# EEPROM_Temp_LEDs.net
KiCad netlist of a schematic drawn in Altium Designer
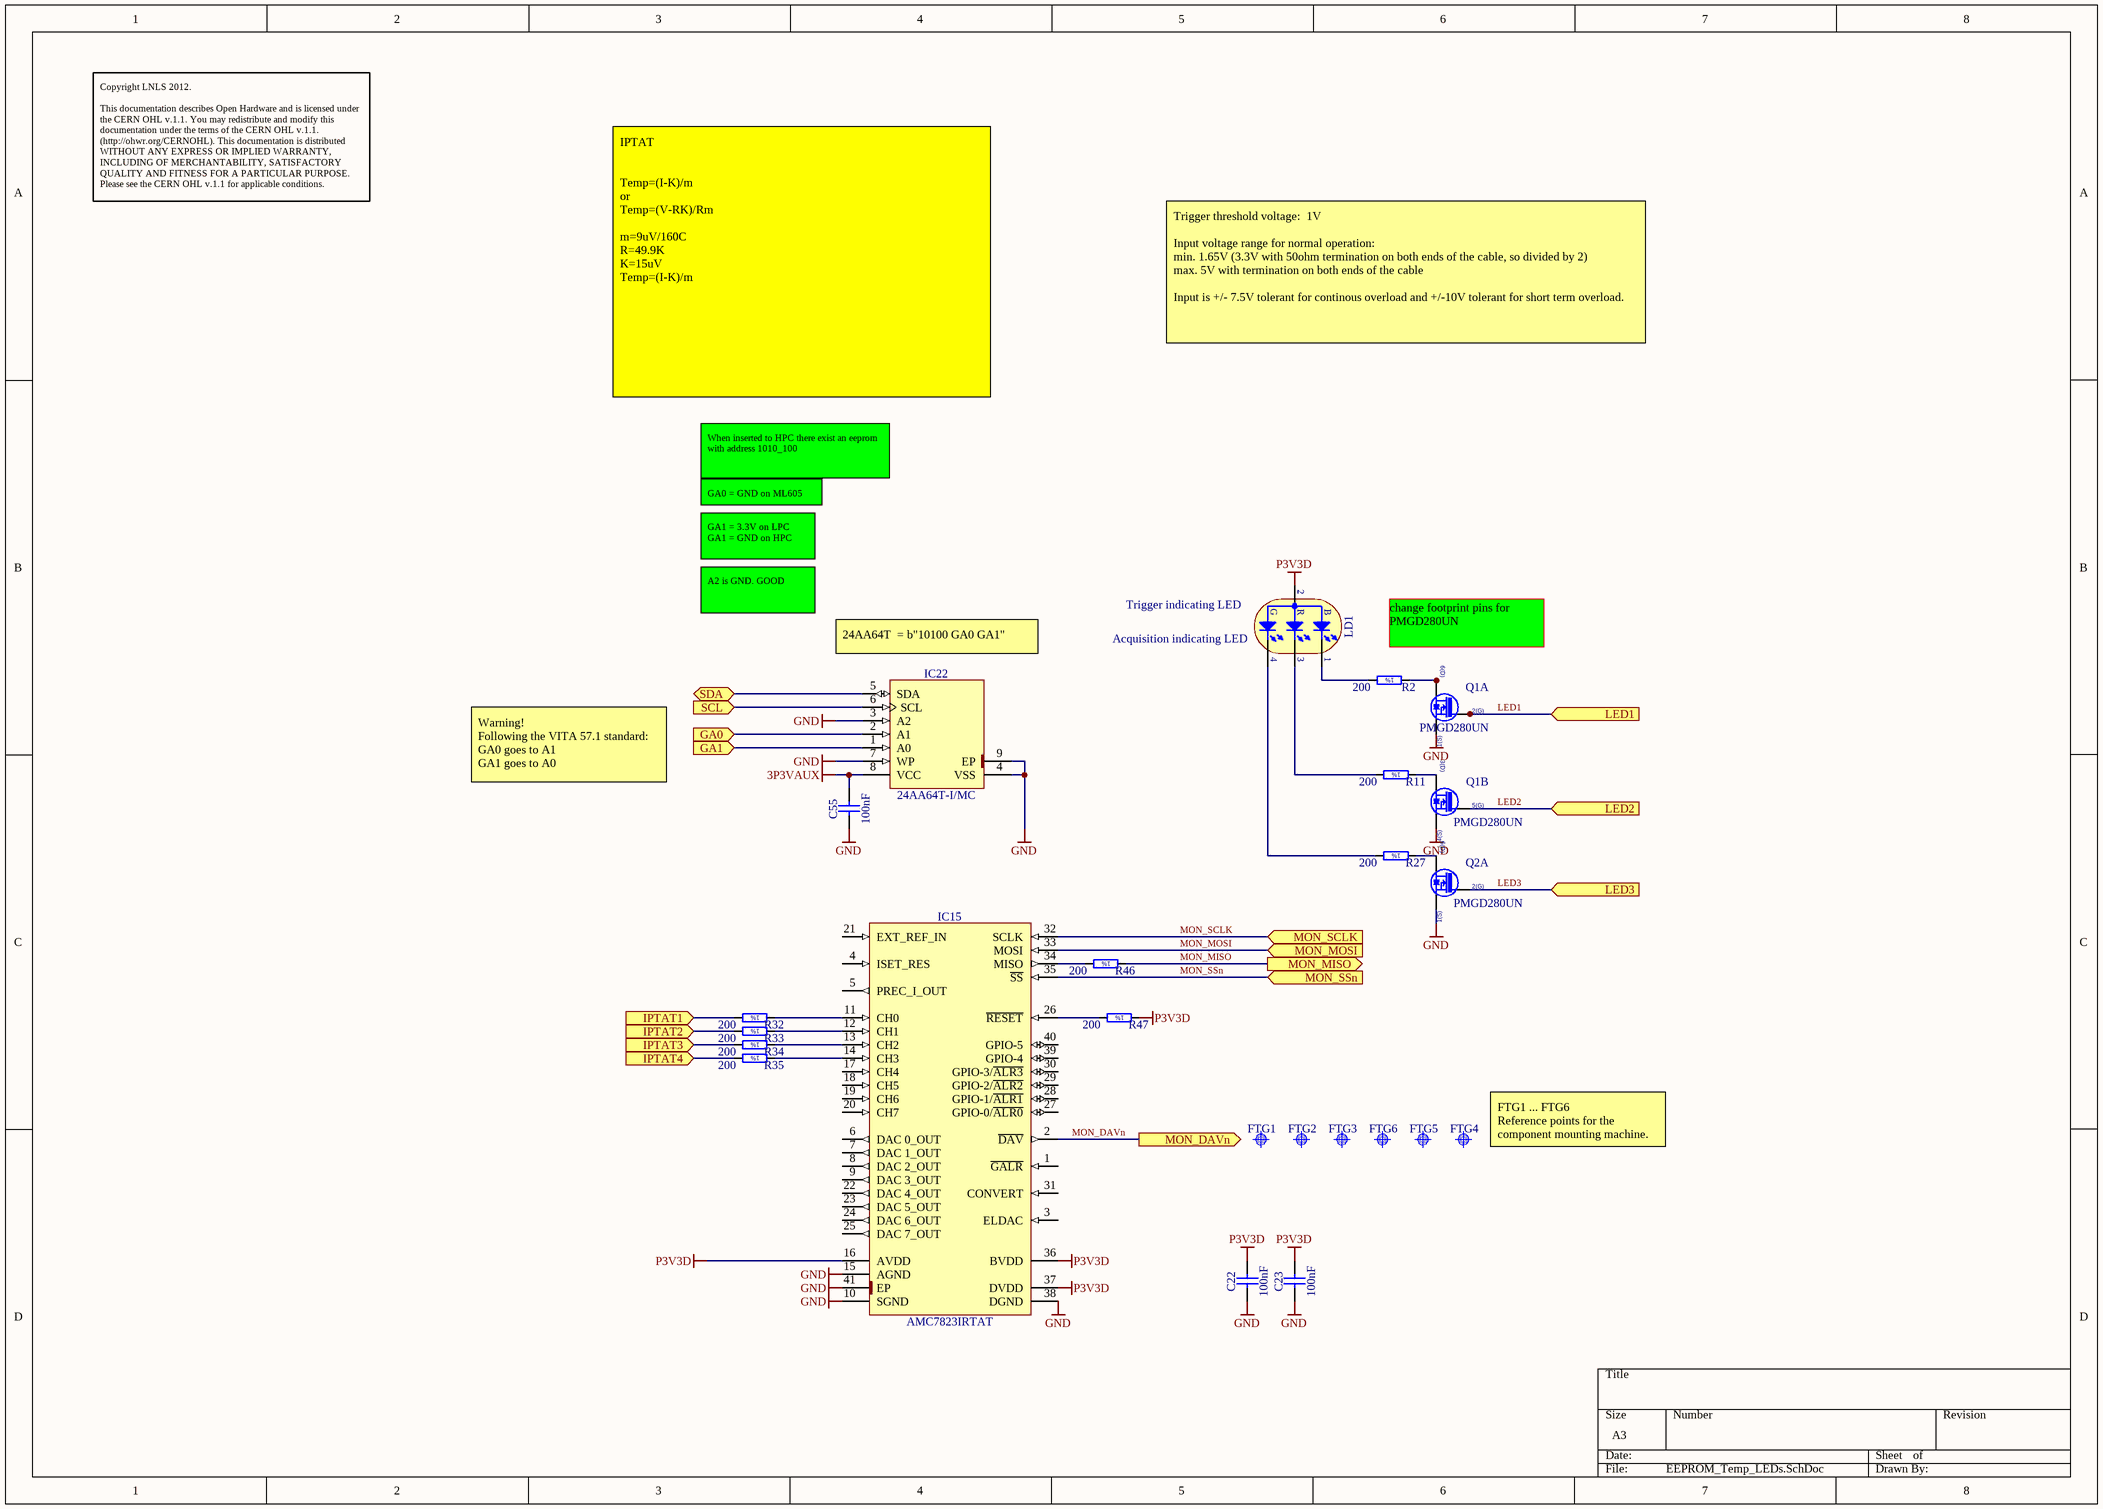
[diagram p0: EEPROM_Temp_LEDs.SchDoc]

(export (version "E")
  (design (tool "Eeschema 10.0.6"))
  (components
    (comp (ref "C22")
      (value "100nF")
      (footprint "CAPC0603X33N")
      (description "Non-polarised capacitor")
      (fields
        (field (name "PART NUMBER") "CC0201_100NF_6.3V_10%_X5R")
        (field (name "VOLTAGE") "6.3V")
        (field (name "AUTHOR") "CERN DEM JLC")
      )
      (libsource (lib "Capacitors") (part "Capacitor - non polarized"))
    )
    (comp (ref "C23")
      (value "100nF")
      (footprint "CAPC0603X33N")
      (description "Non-polarised capacitor")
      (fields
        (field (name "PART NUMBER") "CC0201_100NF_6.3V_10%_X5R")
        (field (name "VOLTAGE") "6.3V")
        (field (name "AUTHOR") "CERN DEM JLC")
      )
      (libsource (lib "Capacitors") (part "Capacitor - non polarized"))
    )
    (comp (ref "C55")
      (value "100nF")
      (footprint "CAPC0603X33N")
      (description "Non-polarised capacitor")
      (fields
        (field (name "PART NUMBER") "CC0201_100NF_6.3V_10%_X5R")
        (field (name "VOLTAGE") "6.3V")
        (field (name "AUTHOR") "CERN DEM JLC")
      )
      (libsource (lib "Capacitors") (part "Capacitor - non polarized"))
    )
    (comp (ref "FTG1")
      (value "Use only in PCB")
      (footprint "FIDUCIAL_TOP_S100-200")
      (description "Fiducial Target")
      (fields (field (name "PART NUMBER") "FIDUCIAL_TARGET_S100-200") (field (name "AUTHOR") "CERN DEM JLC"))
      (libsource (lib "Eletro-mechanical") (part "Fiducial Target"))
    )
    (comp (ref "FTG2")
      (value "Use only in PCB")
      (footprint "FIDUCIAL_TOP_S100-200")
      (description "Fiducial Target")
      (fields (field (name "PART NUMBER") "FIDUCIAL_TARGET_S100-200") (field (name "AUTHOR") "CERN DEM JLC"))
      (libsource (lib "Eletro-mechanical") (part "Fiducial Target"))
    )
    (comp (ref "FTG3")
      (value "Use only in PCB")
      (footprint "FIDUCIAL_TOP_S100-200")
      (description "Fiducial Target")
      (fields (field (name "PART NUMBER") "FIDUCIAL_TARGET_S100-200") (field (name "AUTHOR") "CERN DEM JLC"))
      (libsource (lib "Eletro-mechanical") (part "Fiducial Target"))
    )
    (comp (ref "FTG4")
      (value "Use only in PCB")
      (footprint "FIDUCIAL_TOP_S100-200")
      (description "Fiducial Target")
      (fields (field (name "PART NUMBER") "FIDUCIAL_TARGET_S100-200") (field (name "AUTHOR") "CERN DEM JLC"))
      (libsource (lib "Eletro-mechanical") (part "Fiducial Target"))
    )
    (comp (ref "FTG5")
      (value "Use only in PCB")
      (footprint "FIDUCIAL_TOP_S100-200")
      (description "Fiducial Target")
      (fields (field (name "PART NUMBER") "FIDUCIAL_TARGET_S100-200") (field (name "AUTHOR") "CERN DEM JLC"))
      (libsource (lib "Eletro-mechanical") (part "Fiducial Target"))
    )
    (comp (ref "FTG6")
      (value "Use only in PCB")
      (footprint "FIDUCIAL_TOP_S100-200")
      (description "Fiducial Target")
      (fields (field (name "PART NUMBER") "FIDUCIAL_TARGET_S100-200") (field (name "AUTHOR") "CERN DEM JLC"))
      (libsource (lib "Eletro-mechanical") (part "Fiducial Target"))
    )
    (comp (ref "IC15")
      (value "AMC7823IRTAT")
      (footprint "QFN50P600X600X80-41N-S425")
      (description "Integrated, Multichannel ADC and DAC for Analog Monitoring & Control")
      (fields (field (name "MANUFACTURER") "TEXAS INSTRUMENTS") (field (name "AUTHOR") "CERN DEM JLC"))
      (libsource (lib "ICs And Semiconductors") (part "AMC7823"))
    )
    (comp (ref "IC22")
      (value "24AA64T-I/MC")
      (footprint "SON50P300X200X100-9N-R175X155")
      (description "1.7-5.5V 64K I2C Serial EEPROM")
      (fields (field (name "MANUFACTURER") "MICROCHIP TECHNOLOGY") (field (name "AUTHOR") "CERN DEM JLC"))
      (libsource (lib "ICs And Semiconductors") (part "24AA64T-I/MC"))
    )
    (comp (ref "LD1")
      (value "~")
      (footprint "LED_AVAGO_HSMF-C113")
      (description "Tricolor LEDs 1 Cathode Blue, 2 Common Anode, 3 Cathode Red, 4 Cathode Green")
      (fields
        (field (name "PART NUMBER") "LED_AVAGO_HSMF-C113")
        (field (name "MANUFACTURER") "AVAGO TECHNOLOGIES")
        (field (name "AUTHOR") "CERN DEM JLC")
      )
      (libsource (lib "ICs And Semiconductors") (part "LED Blue-Red-Green 1CB_2AC_3CR_4CG"))
    )
    (comp (ref "Q1")
      (value "PMGD280UN")
      (footprint "SOT65P210X110-6N")
      (description "Dual N-Channel micro TrenchMOS™ Ultra Low Level FET")
      (fields (field (name "MANUFACTURER") "NXP SEMICONDUCTORS") (field (name "AUTHOR") "CERN DEM JLC"))
      (libsource (lib "") (part "PMGD280UN_1"))
    )
    (comp (ref "Q2")
      (value "PMGD280UN")
      (footprint "SOT65P210X110-6N")
      (description "Dual N-Channel micro TrenchMOS™ Ultra Low Level FET")
      (fields (field (name "MANUFACTURER") "NXP SEMICONDUCTORS") (field (name "AUTHOR") "CERN DEM JLC"))
      (libsource (lib "") (part "PMGD280UN_1"))
    )
    (comp (ref "R2")
      (value "200")
      (footprint "RESC1005X40N")
      (description "Resistor - 1%")
      (fields
        (field (name "PART NUMBER") "R0402_200R_1%_0.0625W_100PPM")
        (field (name "POWER") "0.0625W")
        (field (name "AUTHOR") "CERN DEM JLC")
      )
      (libsource (lib "Resistors") (part "Resistor - 1%"))
    )
    (comp (ref "R11")
      (value "200")
      (footprint "RESC1005X40N")
      (description "Resistor - 1%")
      (fields
        (field (name "PART NUMBER") "R0402_200R_1%_0.0625W_100PPM")
        (field (name "POWER") "0.0625W")
        (field (name "AUTHOR") "CERN DEM JLC")
      )
      (libsource (lib "Resistors") (part "Resistor - 1%"))
    )
    (comp (ref "R27")
      (value "200")
      (footprint "RESC1005X40N")
      (description "Resistor - 1%")
      (fields
        (field (name "PART NUMBER") "R0402_200R_1%_0.0625W_100PPM")
        (field (name "POWER") "0.0625W")
        (field (name "AUTHOR") "CERN DEM JLC")
      )
      (libsource (lib "Resistors") (part "Resistor - 1%"))
    )
    (comp (ref "R32")
      (value "200")
      (footprint "RESC1005X40N")
      (description "Resistor - 1%")
      (fields
        (field (name "PART NUMBER") "R0402_200R_1%_0.0625W_100PPM")
        (field (name "POWER") "0.0625W")
        (field (name "AUTHOR") "CERN DEM JLC")
      )
      (libsource (lib "Resistors") (part "Resistor - 1%"))
    )
    (comp (ref "R33")
      (value "200")
      (footprint "RESC1005X40N")
      (description "Resistor - 1%")
      (fields
        (field (name "PART NUMBER") "R0402_200R_1%_0.0625W_100PPM")
        (field (name "POWER") "0.0625W")
        (field (name "AUTHOR") "CERN DEM JLC")
      )
      (libsource (lib "Resistors") (part "Resistor - 1%"))
    )
    (comp (ref "R34")
      (value "200")
      (footprint "RESC1005X40N")
      (description "Resistor - 1%")
      (fields
        (field (name "PART NUMBER") "R0402_200R_1%_0.0625W_100PPM")
        (field (name "POWER") "0.0625W")
        (field (name "AUTHOR") "CERN DEM JLC")
      )
      (libsource (lib "Resistors") (part "Resistor - 1%"))
    )
    (comp (ref "R35")
      (value "200")
      (footprint "RESC1005X40N")
      (description "Resistor - 1%")
      (fields
        (field (name "PART NUMBER") "R0402_200R_1%_0.0625W_100PPM")
        (field (name "POWER") "0.0625W")
        (field (name "AUTHOR") "CERN DEM JLC")
      )
      (libsource (lib "Resistors") (part "Resistor - 1%"))
    )
    (comp (ref "R46")
      (value "200")
      (footprint "RESC1005X40N")
      (description "Resistor - 1%")
      (fields
        (field (name "PART NUMBER") "R0402_200R_1%_0.0625W_100PPM")
        (field (name "POWER") "0.0625W")
        (field (name "AUTHOR") "CERN DEM JLC")
      )
      (libsource (lib "Resistors") (part "Resistor - 1%"))
    )
    (comp (ref "R47")
      (value "200")
      (footprint "RESC1005X40N")
      (description "Resistor - 1%")
      (fields
        (field (name "PART NUMBER") "R0402_200R_1%_0.0625W_100PPM")
        (field (name "POWER") "0.0625W")
        (field (name "AUTHOR") "CERN DEM JLC")
      )
      (libsource (lib "Resistors") (part "Resistor - 1%"))
    )
  )
  (nets
    (net (code "1") (name "/GA0") (class "Default")
      (node (ref "IC22") (pin "2") (pinfunction "A1_2") (pintype "input"))
    )
    (net (code "2") (name "/GA1") (class "Default")
      (node (ref "IC22") (pin "1") (pinfunction "A0_1") (pintype "input"))
    )
    (net (code "3") (name "/IPTAT1") (class "Default")
      (node (ref "R32") (pin "2") (pinfunction "2_2") (pintype "passive"))
    )
    (net (code "4") (name "/IPTAT2") (class "Default")
      (node (ref "R33") (pin "2") (pinfunction "2_2") (pintype "passive"))
    )
    (net (code "5") (name "/IPTAT3") (class "Default")
      (node (ref "R34") (pin "2") (pinfunction "2_2") (pintype "passive"))
    )
    (net (code "6") (name "/IPTAT4") (class "Default")
      (node (ref "R35") (pin "2") (pinfunction "2_2") (pintype "passive"))
    )
    (net (code "7") (name "/LED1") (class "Default")
      (node (ref "Q1") (pin "2") (pinfunction "G_2") (pintype "passive"))
    )
    (net (code "8") (name "/LED2") (class "Default")
      (node (ref "Q1") (pin "5") (pinfunction "G_5") (pintype "passive"))
    )
    (net (code "9") (name "/LED3") (class "Default")
      (node (ref "Q2") (pin "2") (pinfunction "G_2") (pintype "passive"))
    )
    (net (code "10") (name "/MON_DAVn") (class "Default")
      (node (ref "IC15") (pin "2") (pinfunction "~{DAV}_2") (pintype "output"))
    )
    (net (code "11") (name "/MON_MISO") (class "Default")
      (node (ref "R46") (pin "1") (pinfunction "1_1") (pintype "passive"))
    )
    (net (code "12") (name "/MON_MOSI") (class "Default")
      (node (ref "IC15") (pin "33") (pinfunction "MOSI_33") (pintype "input"))
    )
    (net (code "13") (name "/MON_SCLK") (class "Default")
      (node (ref "IC15") (pin "32") (pinfunction "SCLK_32") (pintype "input"))
    )
    (net (code "14") (name "/MON_SSn") (class "Default")
      (node (ref "IC15") (pin "35") (pinfunction "~{SS}_35") (pintype "input"))
    )
    (net (code "15") (name "/SCL") (class "Default")
      (node (ref "IC22") (pin "6") (pinfunction "SCL_6") (pintype "input"))
    )
    (net (code "16") (name "/SDA") (class "Default")
      (node (ref "IC22") (pin "5") (pinfunction "SDA_5") (pintype "bidirectional"))
    )
    (net (code "17") (name "3P3VAUX") (class "Default")
      (node (ref "C55") (pin "2") (pinfunction "2_2") (pintype "passive"))
      (node (ref "IC22") (pin "8") (pinfunction "VCC_8") (pintype "power_in"))
    )
    (net (code "18") (name "GND") (class "Default")
      (node (ref "C22") (pin "1") (pinfunction "1_1") (pintype "passive"))
      (node (ref "C23") (pin "1") (pinfunction "1_1") (pintype "passive"))
      (node (ref "C55") (pin "1") (pinfunction "1_1") (pintype "passive"))
      (node (ref "IC15") (pin "10") (pinfunction "SGND_10") (pintype "power_in"))
      (node (ref "IC15") (pin "15") (pinfunction "AGND_15") (pintype "power_in"))
      (node (ref "IC15") (pin "38") (pinfunction "DGND_38") (pintype "power_in"))
      (node (ref "IC15") (pin "41") (pinfunction "EP_41") (pintype "power_in"))
      (node (ref "IC22") (pin "3") (pinfunction "A2_3") (pintype "input"))
      (node (ref "IC22") (pin "4") (pinfunction "VSS_4") (pintype "power_in"))
      (node (ref "IC22") (pin "7") (pinfunction "WP_7") (pintype "input"))
      (node (ref "IC22") (pin "9") (pinfunction "EP_9") (pintype "power_in"))
      (node (ref "Q1") (pin "1") (pinfunction "S_1") (pintype "passive"))
      (node (ref "Q1") (pin "4") (pinfunction "S_4") (pintype "passive"))
      (node (ref "Q2") (pin "1") (pinfunction "S_1") (pintype "passive"))
    )
    (net (code "19") (name "Net-(IC15-CH0)") (class "Default")
      (node (ref "IC15") (pin "11") (pinfunction "CH0_11") (pintype "input"))
      (node (ref "R32") (pin "1") (pinfunction "1_1") (pintype "passive"))
    )
    (net (code "20") (name "Net-(IC15-CH1)") (class "Default")
      (node (ref "IC15") (pin "12") (pinfunction "CH1_12") (pintype "input"))
      (node (ref "R33") (pin "1") (pinfunction "1_1") (pintype "passive"))
    )
    (net (code "21") (name "Net-(IC15-CH2)") (class "Default")
      (node (ref "IC15") (pin "13") (pinfunction "CH2_13") (pintype "input"))
      (node (ref "R34") (pin "1") (pinfunction "1_1") (pintype "passive"))
    )
    (net (code "22") (name "Net-(IC15-CH3)") (class "Default")
      (node (ref "IC15") (pin "14") (pinfunction "CH3_14") (pintype "input"))
      (node (ref "R35") (pin "1") (pinfunction "1_1") (pintype "passive"))
    )
    (net (code "23") (name "Net-(IC15-MISO)") (class "Default")
      (node (ref "IC15") (pin "34") (pinfunction "MISO_34") (pintype "output"))
      (node (ref "R46") (pin "2") (pinfunction "2_2") (pintype "passive"))
    )
    (net (code "24") (name "Net-(IC15-~{RESET})") (class "Default")
      (node (ref "IC15") (pin "26") (pinfunction "~{RESET}_26") (pintype "input"))
      (node (ref "R47") (pin "2") (pinfunction "2_2") (pintype "passive"))
    )
    (net (code "25") (name "Net-(LD1-CB)") (class "Default")
      (node (ref "LD1") (pin "1") (pinfunction "CB_1") (pintype "passive"))
      (node (ref "R2") (pin "2") (pinfunction "2_2") (pintype "passive"))
    )
    (net (code "26") (name "Net-(LD1-CG)") (class "Default")
      (node (ref "LD1") (pin "4") (pinfunction "CG_4") (pintype "passive"))
      (node (ref "R27") (pin "2") (pinfunction "2_2") (pintype "passive"))
    )
    (net (code "27") (name "Net-(LD1-CR)") (class "Default")
      (node (ref "LD1") (pin "3") (pinfunction "CR_3") (pintype "passive"))
      (node (ref "R11") (pin "2") (pinfunction "2_2") (pintype "passive"))
    )
    (net (code "28") (name "Net-(Q1A-D)") (class "Default")
      (node (ref "Q1") (pin "6") (pinfunction "D_6") (pintype "passive"))
      (node (ref "R2") (pin "1") (pinfunction "1_1") (pintype "passive"))
    )
    (net (code "29") (name "Net-(Q1B-D)") (class "Default")
      (node (ref "Q1") (pin "3") (pinfunction "D_3") (pintype "passive"))
      (node (ref "R11") (pin "1") (pinfunction "1_1") (pintype "passive"))
    )
    (net (code "30") (name "Net-(Q2A-D)") (class "Default")
      (node (ref "Q2") (pin "6") (pinfunction "D_6") (pintype "passive"))
      (node (ref "R27") (pin "1") (pinfunction "1_1") (pintype "passive"))
    )
    (net (code "31") (name "P3V3D") (class "Default")
      (node (ref "C22") (pin "2") (pinfunction "2_2") (pintype "passive"))
      (node (ref "C23") (pin "2") (pinfunction "2_2") (pintype "passive"))
      (node (ref "IC15") (pin "16") (pinfunction "AVDD_16") (pintype "power_in"))
      (node (ref "IC15") (pin "36") (pinfunction "BVDD_36") (pintype "power_in"))
      (node (ref "IC15") (pin "37") (pinfunction "DVDD_37") (pintype "power_in"))
      (node (ref "LD1") (pin "2") (pinfunction "AC_2") (pintype "passive"))
      (node (ref "R47") (pin "1") (pinfunction "1_1") (pintype "passive"))
    )
    (net (code "32") (name "unconnected-(IC15-CH4-Pad17)") (class "Default")
      (node (ref "IC15") (pin "17") (pinfunction "CH4_17") (pintype "input"))
    )
    (net (code "33") (name "unconnected-(IC15-CH5-Pad18)") (class "Default")
      (node (ref "IC15") (pin "18") (pinfunction "CH5_18") (pintype "input"))
    )
    (net (code "34") (name "unconnected-(IC15-CH6-Pad19)") (class "Default")
      (node (ref "IC15") (pin "19") (pinfunction "CH6_19") (pintype "input"))
    )
    (net (code "35") (name "unconnected-(IC15-CH7-Pad20)") (class "Default")
      (node (ref "IC15") (pin "20") (pinfunction "CH7_20") (pintype "input"))
    )
    (net (code "36") (name "unconnected-(IC15-CONVERT-Pad31)") (class "Default")
      (node (ref "IC15") (pin "31") (pinfunction "CONVERT_31") (pintype "input"))
    )
    (net (code "37") (name "unconnected-(IC15-DAC_0_OUT-Pad6)") (class "Default")
      (node (ref "IC15") (pin "6") (pinfunction "DAC_0_OUT_6") (pintype "output"))
    )
    (net (code "38") (name "unconnected-(IC15-DAC_1_OUT-Pad7)") (class "Default")
      (node (ref "IC15") (pin "7") (pinfunction "DAC_1_OUT_7") (pintype "output"))
    )
    (net (code "39") (name "unconnected-(IC15-DAC_2_OUT-Pad8)") (class "Default")
      (node (ref "IC15") (pin "8") (pinfunction "DAC_2_OUT_8") (pintype "output"))
    )
    (net (code "40") (name "unconnected-(IC15-DAC_3_OUT-Pad9)") (class "Default")
      (node (ref "IC15") (pin "9") (pinfunction "DAC_3_OUT_9") (pintype "output"))
    )
    (net (code "41") (name "unconnected-(IC15-DAC_4_OUT-Pad22)") (class "Default")
      (node (ref "IC15") (pin "22") (pinfunction "DAC_4_OUT_22") (pintype "output"))
    )
    (net (code "42") (name "unconnected-(IC15-DAC_5_OUT-Pad23)") (class "Default")
      (node (ref "IC15") (pin "23") (pinfunction "DAC_5_OUT_23") (pintype "output"))
    )
    (net (code "43") (name "unconnected-(IC15-DAC_6_OUT-Pad24)") (class "Default")
      (node (ref "IC15") (pin "24") (pinfunction "DAC_6_OUT_24") (pintype "output"))
    )
    (net (code "44") (name "unconnected-(IC15-DAC_7_OUT-Pad25)") (class "Default")
      (node (ref "IC15") (pin "25") (pinfunction "DAC_7_OUT_25") (pintype "output"))
    )
    (net (code "45") (name "unconnected-(IC15-ELDAC-Pad3)") (class "Default")
      (node (ref "IC15") (pin "3") (pinfunction "ELDAC_3") (pintype "input"))
    )
    (net (code "46") (name "unconnected-(IC15-EXT_REF_IN-Pad21)") (class "Default")
      (node (ref "IC15") (pin "21") (pinfunction "EXT_REF_IN_21") (pintype "input"))
    )
    (net (code "47") (name "unconnected-(IC15-GPIO-0{slash}~{ALR0}-Pad27)") (class "Default")
      (node (ref "IC15") (pin "27") (pinfunction "GPIO-0/~{ALR0}_27") (pintype "bidirectional"))
    )
    (net (code "48") (name "unconnected-(IC15-GPIO-1{slash}~{ALR1}-Pad28)") (class "Default")
      (node (ref "IC15") (pin "28") (pinfunction "GPIO-1/~{ALR1}_28") (pintype "bidirectional"))
    )
    (net (code "49") (name "unconnected-(IC15-GPIO-2{slash}~{ALR2}-Pad29)") (class "Default")
      (node (ref "IC15") (pin "29") (pinfunction "GPIO-2/~{ALR2}_29") (pintype "bidirectional"))
    )
    (net (code "50") (name "unconnected-(IC15-GPIO-3{slash}~{ALR3}-Pad30)") (class "Default")
      (node (ref "IC15") (pin "30") (pinfunction "GPIO-3/~{ALR3}_30") (pintype "bidirectional"))
    )
    (net (code "51") (name "unconnected-(IC15-GPIO-4-Pad39)") (class "Default")
      (node (ref "IC15") (pin "39") (pinfunction "GPIO-4_39") (pintype "bidirectional"))
    )
    (net (code "52") (name "unconnected-(IC15-GPIO-5-Pad40)") (class "Default")
      (node (ref "IC15") (pin "40") (pinfunction "GPIO-5_40") (pintype "bidirectional"))
    )
    (net (code "53") (name "unconnected-(IC15-ISET_RES-Pad4)") (class "Default")
      (node (ref "IC15") (pin "4") (pinfunction "ISET_RES_4") (pintype "input"))
    )
    (net (code "54") (name "unconnected-(IC15-PREC_I_OUT-Pad5)") (class "Default")
      (node (ref "IC15") (pin "5") (pinfunction "PREC_I_OUT_5") (pintype "output"))
    )
    (net (code "55") (name "unconnected-(IC15-~{GALR}-Pad1)") (class "Default")
      (node (ref "IC15") (pin "1") (pinfunction "~{GALR}_1") (pintype "input"))
    )
  )
)
